# Adapter_UNIT_SPI_TO_HDMI.net
KiCad netlist of a schematic drawn in Altium Designer
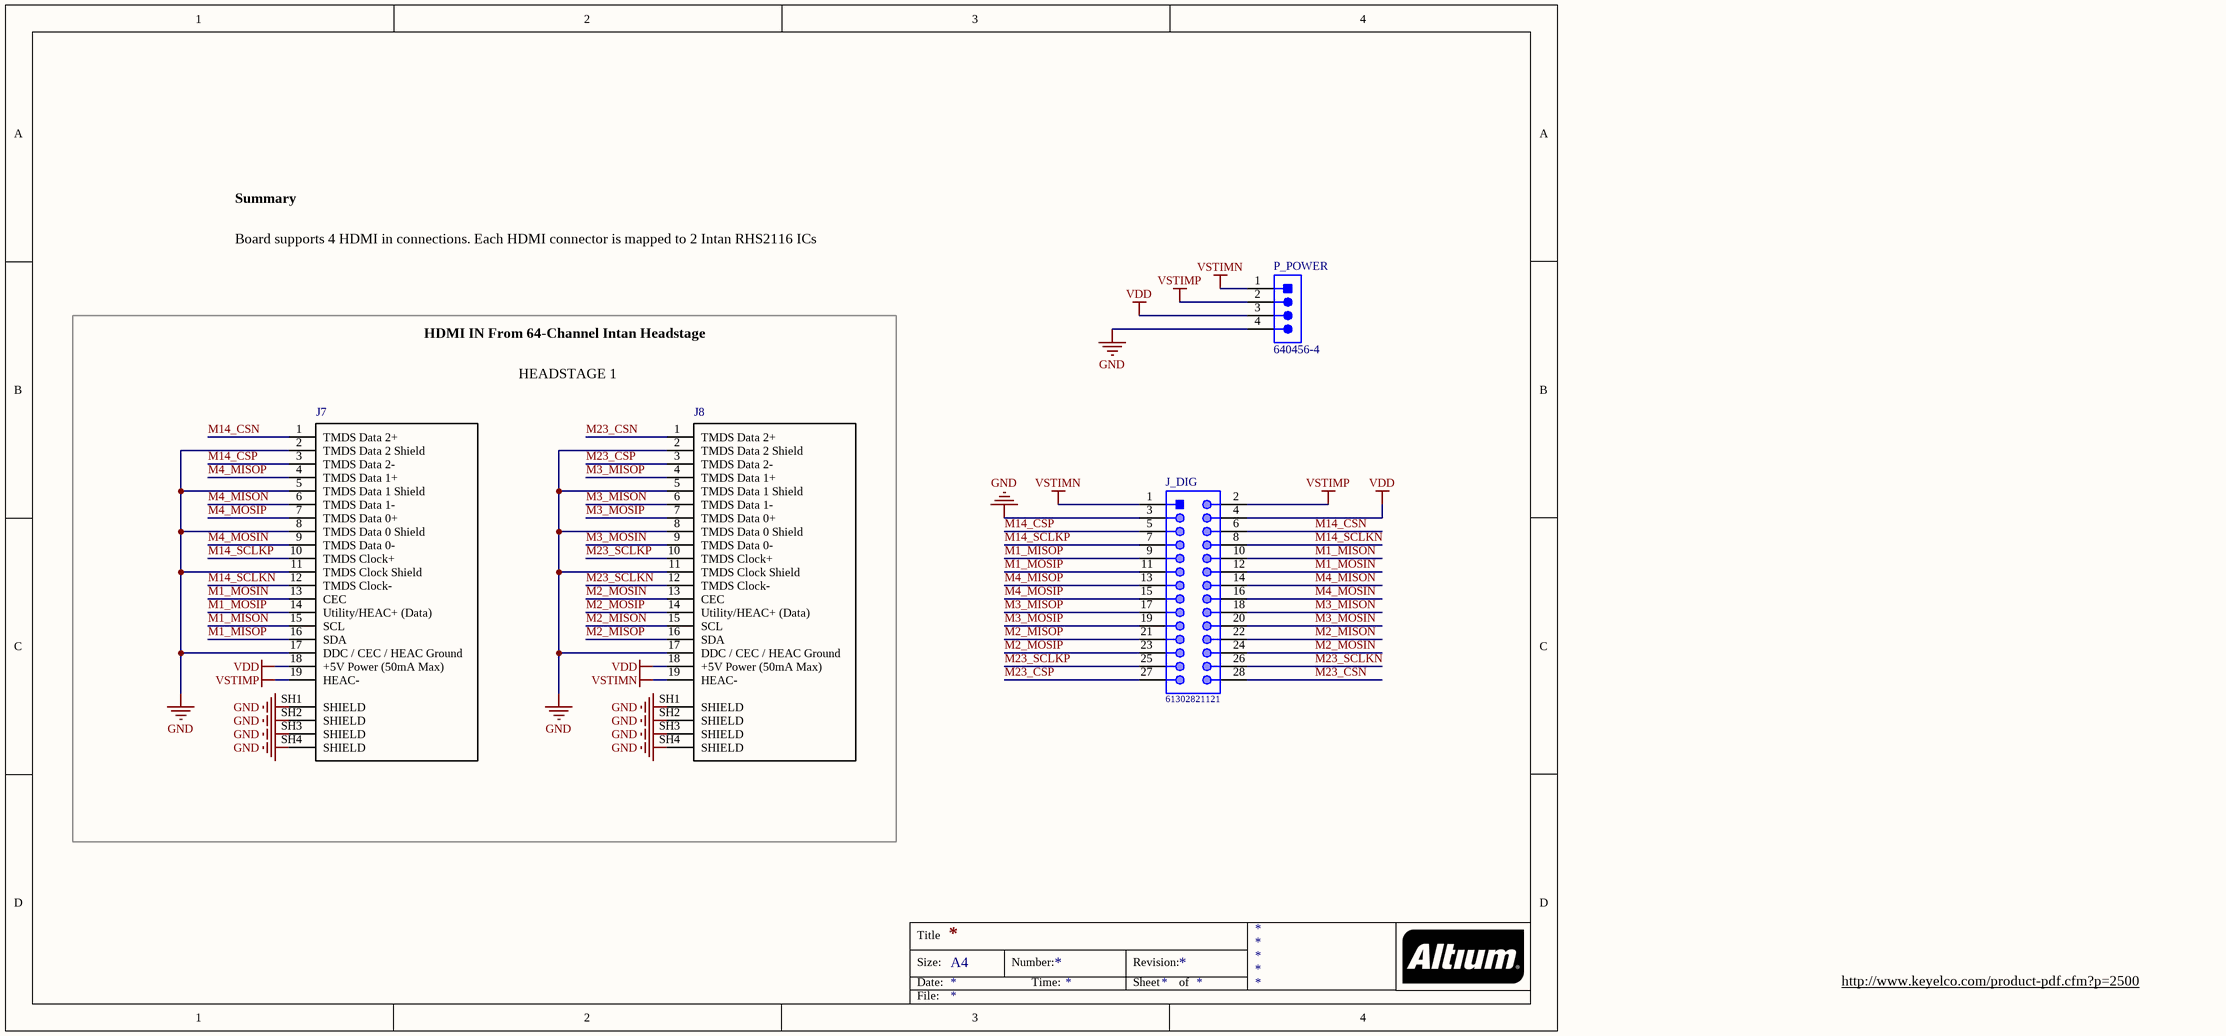
[diagram p0: Adapter_UNIT_SPI_TO_HDMI.SchDoc]

(export (version "E")
  (design (tool "Eeschema 10.0.6"))
  (components
    (comp (ref "J7")
      (value "1747981-2")
      (footprint "te_connectivity_audio_video_connectors:TE_1747981-2_1747981-2(Primary)")
      (description "Conn HDMI RCP 19 POS 0.5mm Solder ST SMD 19 Terminal 1 Port T/R")
      (fields (field (name "MF") "TE Connectivity"))
      (libsource (lib "te_connectivity_audio_video_connectors") (part "1747981-2"))
    )
    (comp (ref "J8")
      (value "1747981-2")
      (footprint "te_connectivity_audio_video_connectors:TE_1747981-2_1747981-2(Primary)")
      (description "Conn HDMI RCP 19 POS 0.5mm Solder ST SMD 19 Terminal 1 Port T/R")
      (fields (field (name "MF") "TE Connectivity"))
      (libsource (lib "te_connectivity_audio_video_connectors") (part "1747981-2"))
    )
    (comp (ref "J_DIG")
      (value "61302821121")
      (footprint "61302821121")
      (description "THT Vertical Pin Header WR-PHD, Pitch 2.54 mm, Dual Row, 28 pins")
      (fields (field (name "MANUFACTURER") "Wurth Elektronik") (field (name "PUBLISHER") "WurthElektronik"))
      (libsource (lib "Altium Content Vault") (part "WE-CN-2P-M-R28"))
    )
    (comp (ref "P_POWER")
      (value "640456-4")
      (footprint "TECO-640456-4")
      (description "Male Header, Pitch 2.54 mm, 1 x 4 Position, Height 10.03 mm, Tail Length 3.56 mm, RoHS, Bulk")
      (fields (field (name "MANUFACTURER") "TE Connectivity"))
      (libsource (lib "Altium Content Vault") (part "CN-1P-M-R4"))
    )
  )
  (nets
    (net (code "1") (name "/M1_MISON") (class "Default")
      (node (ref "J7") (pin "15") (pinfunction "SCL_15") (pintype "passive"))
      (node (ref "J_DIG") (pin "10") (pinfunction "10_10") (pintype "passive"))
    )
    (net (code "2") (name "/M1_MISOP") (class "Default")
      (node (ref "J7") (pin "16") (pinfunction "SDA_16") (pintype "passive"))
      (node (ref "J_DIG") (pin "9") (pinfunction "9_9") (pintype "passive"))
    )
    (net (code "3") (name "/M1_MOSIN") (class "Default")
      (node (ref "J7") (pin "13") (pinfunction "CEC_13") (pintype "passive"))
      (node (ref "J_DIG") (pin "12") (pinfunction "12_12") (pintype "passive"))
    )
    (net (code "4") (name "/M1_MOSIP") (class "Default")
      (node (ref "J7") (pin "14") (pinfunction "Utility/HEAC+_(Data)_14") (pintype "passive"))
      (node (ref "J_DIG") (pin "11") (pinfunction "11_11") (pintype "passive"))
    )
    (net (code "5") (name "/M2_MISON") (class "Default")
      (node (ref "J8") (pin "15") (pinfunction "SCL_15") (pintype "passive"))
      (node (ref "J_DIG") (pin "22") (pinfunction "22_22") (pintype "passive"))
    )
    (net (code "6") (name "/M2_MISOP") (class "Default")
      (node (ref "J8") (pin "16") (pinfunction "SDA_16") (pintype "passive"))
      (node (ref "J_DIG") (pin "21") (pinfunction "21_21") (pintype "passive"))
    )
    (net (code "7") (name "/M2_MOSIN") (class "Default")
      (node (ref "J8") (pin "13") (pinfunction "CEC_13") (pintype "passive"))
      (node (ref "J_DIG") (pin "24") (pinfunction "24_24") (pintype "passive"))
    )
    (net (code "8") (name "/M2_MOSIP") (class "Default")
      (node (ref "J8") (pin "14") (pinfunction "Utility/HEAC+_(Data)_14") (pintype "passive"))
      (node (ref "J_DIG") (pin "23") (pinfunction "23_23") (pintype "passive"))
    )
    (net (code "9") (name "/M3_MISON") (class "Default")
      (node (ref "J8") (pin "6") (pinfunction "TMDS_Data_1-_6") (pintype "passive"))
      (node (ref "J_DIG") (pin "18") (pinfunction "18_18") (pintype "passive"))
    )
    (net (code "10") (name "/M3_MISOP") (class "Default")
      (node (ref "J8") (pin "4") (pinfunction "TMDS_Data_1+_4") (pintype "passive"))
      (node (ref "J_DIG") (pin "17") (pinfunction "17_17") (pintype "passive"))
    )
    (net (code "11") (name "/M3_MOSIN") (class "Default")
      (node (ref "J8") (pin "9") (pinfunction "TMDS_Data_0-_9") (pintype "passive"))
      (node (ref "J_DIG") (pin "20") (pinfunction "20_20") (pintype "passive"))
    )
    (net (code "12") (name "/M3_MOSIP") (class "Default")
      (node (ref "J8") (pin "7") (pinfunction "TMDS_Data_0+_7") (pintype "passive"))
      (node (ref "J_DIG") (pin "19") (pinfunction "19_19") (pintype "passive"))
    )
    (net (code "13") (name "/M4_MISON") (class "Default")
      (node (ref "J7") (pin "6") (pinfunction "TMDS_Data_1-_6") (pintype "passive"))
      (node (ref "J_DIG") (pin "14") (pinfunction "14_14") (pintype "passive"))
    )
    (net (code "14") (name "/M4_MISOP") (class "Default")
      (node (ref "J7") (pin "4") (pinfunction "TMDS_Data_1+_4") (pintype "passive"))
      (node (ref "J_DIG") (pin "13") (pinfunction "13_13") (pintype "passive"))
    )
    (net (code "15") (name "/M4_MOSIN") (class "Default")
      (node (ref "J7") (pin "9") (pinfunction "TMDS_Data_0-_9") (pintype "passive"))
      (node (ref "J_DIG") (pin "16") (pinfunction "16_16") (pintype "passive"))
    )
    (net (code "16") (name "/M4_MOSIP") (class "Default")
      (node (ref "J7") (pin "7") (pinfunction "TMDS_Data_0+_7") (pintype "passive"))
      (node (ref "J_DIG") (pin "15") (pinfunction "15_15") (pintype "passive"))
    )
    (net (code "17") (name "/M14_CSN") (class "Default")
      (node (ref "J7") (pin "1") (pinfunction "TMDS_Data_2+_1") (pintype "passive"))
      (node (ref "J_DIG") (pin "6") (pinfunction "6_6") (pintype "passive"))
    )
    (net (code "18") (name "/M14_CSP") (class "Default")
      (node (ref "J7") (pin "3") (pinfunction "TMDS_Data_2-_3") (pintype "passive"))
      (node (ref "J_DIG") (pin "5") (pinfunction "5_5") (pintype "passive"))
    )
    (net (code "19") (name "/M14_SCLKN") (class "Default")
      (node (ref "J7") (pin "12") (pinfunction "TMDS_Clock-_12") (pintype "passive"))
      (node (ref "J_DIG") (pin "8") (pinfunction "8_8") (pintype "passive"))
    )
    (net (code "20") (name "/M14_SCLKP") (class "Default")
      (node (ref "J7") (pin "10") (pinfunction "TMDS_Clock+_10") (pintype "passive"))
      (node (ref "J_DIG") (pin "7") (pinfunction "7_7") (pintype "passive"))
    )
    (net (code "21") (name "/M23_CSN") (class "Default")
      (node (ref "J8") (pin "1") (pinfunction "TMDS_Data_2+_1") (pintype "passive"))
      (node (ref "J_DIG") (pin "28") (pinfunction "28_28") (pintype "passive"))
    )
    (net (code "22") (name "/M23_CSP") (class "Default")
      (node (ref "J8") (pin "3") (pinfunction "TMDS_Data_2-_3") (pintype "passive"))
      (node (ref "J_DIG") (pin "27") (pinfunction "27_27") (pintype "passive"))
    )
    (net (code "23") (name "/M23_SCLKN") (class "Default")
      (node (ref "J8") (pin "12") (pinfunction "TMDS_Clock-_12") (pintype "passive"))
      (node (ref "J_DIG") (pin "26") (pinfunction "26_26") (pintype "passive"))
    )
    (net (code "24") (name "/M23_SCLKP") (class "Default")
      (node (ref "J8") (pin "10") (pinfunction "TMDS_Clock+_10") (pintype "passive"))
      (node (ref "J_DIG") (pin "25") (pinfunction "25_25") (pintype "passive"))
    )
    (net (code "25") (name "GND") (class "Default")
      (node (ref "J7") (pin "11") (pinfunction "TMDS_Clock_Shield_11") (pintype "passive"))
      (node (ref "J7") (pin "17") (pinfunction "DDC_/_CEC_/_HEAC_Ground_17") (pintype "passive"))
      (node (ref "J7") (pin "2") (pinfunction "TMDS_Data_2_Shield_2") (pintype "passive"))
      (node (ref "J7") (pin "5") (pinfunction "TMDS_Data_1_Shield_5") (pintype "passive"))
      (node (ref "J7") (pin "8") (pinfunction "TMDS_Data_0_Shield_8") (pintype "passive"))
      (node (ref "J7") (pin "SH1") (pinfunction "SHIELD_SH1") (pintype "passive"))
      (node (ref "J7") (pin "SH2") (pinfunction "SHIELD_SH2") (pintype "passive"))
      (node (ref "J7") (pin "SH3") (pinfunction "SHIELD_SH3") (pintype "passive"))
      (node (ref "J7") (pin "SH4") (pinfunction "SHIELD_SH4") (pintype "passive"))
      (node (ref "J8") (pin "11") (pinfunction "TMDS_Clock_Shield_11") (pintype "passive"))
      (node (ref "J8") (pin "17") (pinfunction "DDC_/_CEC_/_HEAC_Ground_17") (pintype "passive"))
      (node (ref "J8") (pin "2") (pinfunction "TMDS_Data_2_Shield_2") (pintype "passive"))
      (node (ref "J8") (pin "5") (pinfunction "TMDS_Data_1_Shield_5") (pintype "passive"))
      (node (ref "J8") (pin "8") (pinfunction "TMDS_Data_0_Shield_8") (pintype "passive"))
      (node (ref "J8") (pin "SH1") (pinfunction "SHIELD_SH1") (pintype "passive"))
      (node (ref "J8") (pin "SH2") (pinfunction "SHIELD_SH2") (pintype "passive"))
      (node (ref "J8") (pin "SH3") (pinfunction "SHIELD_SH3") (pintype "passive"))
      (node (ref "J8") (pin "SH4") (pinfunction "SHIELD_SH4") (pintype "passive"))
      (node (ref "J_DIG") (pin "3") (pinfunction "3_3") (pintype "passive"))
      (node (ref "P_POWER") (pin "4") (pinfunction "4_4") (pintype "passive"))
    )
    (net (code "26") (name "VDD") (class "Default")
      (node (ref "J7") (pin "18") (pinfunction "+5V_Power_(50mA_Max)_18") (pintype "passive"))
      (node (ref "J8") (pin "18") (pinfunction "+5V_Power_(50mA_Max)_18") (pintype "passive"))
      (node (ref "J_DIG") (pin "4") (pinfunction "4_4") (pintype "passive"))
      (node (ref "P_POWER") (pin "3") (pinfunction "3_3") (pintype "passive"))
    )
    (net (code "27") (name "VSTIMN") (class "Default")
      (node (ref "J8") (pin "19") (pinfunction "HEAC-_19") (pintype "passive"))
      (node (ref "J_DIG") (pin "1") (pinfunction "1_1") (pintype "passive"))
      (node (ref "P_POWER") (pin "1") (pinfunction "1_1") (pintype "passive"))
    )
    (net (code "28") (name "VSTIMP") (class "Default")
      (node (ref "J7") (pin "19") (pinfunction "HEAC-_19") (pintype "passive"))
      (node (ref "J_DIG") (pin "2") (pinfunction "2_2") (pintype "passive"))
      (node (ref "P_POWER") (pin "2") (pinfunction "2_2") (pintype "passive"))
    )
  )
)
